# mixer.net
KiCad netlist of a schematic drawn in EAGLE
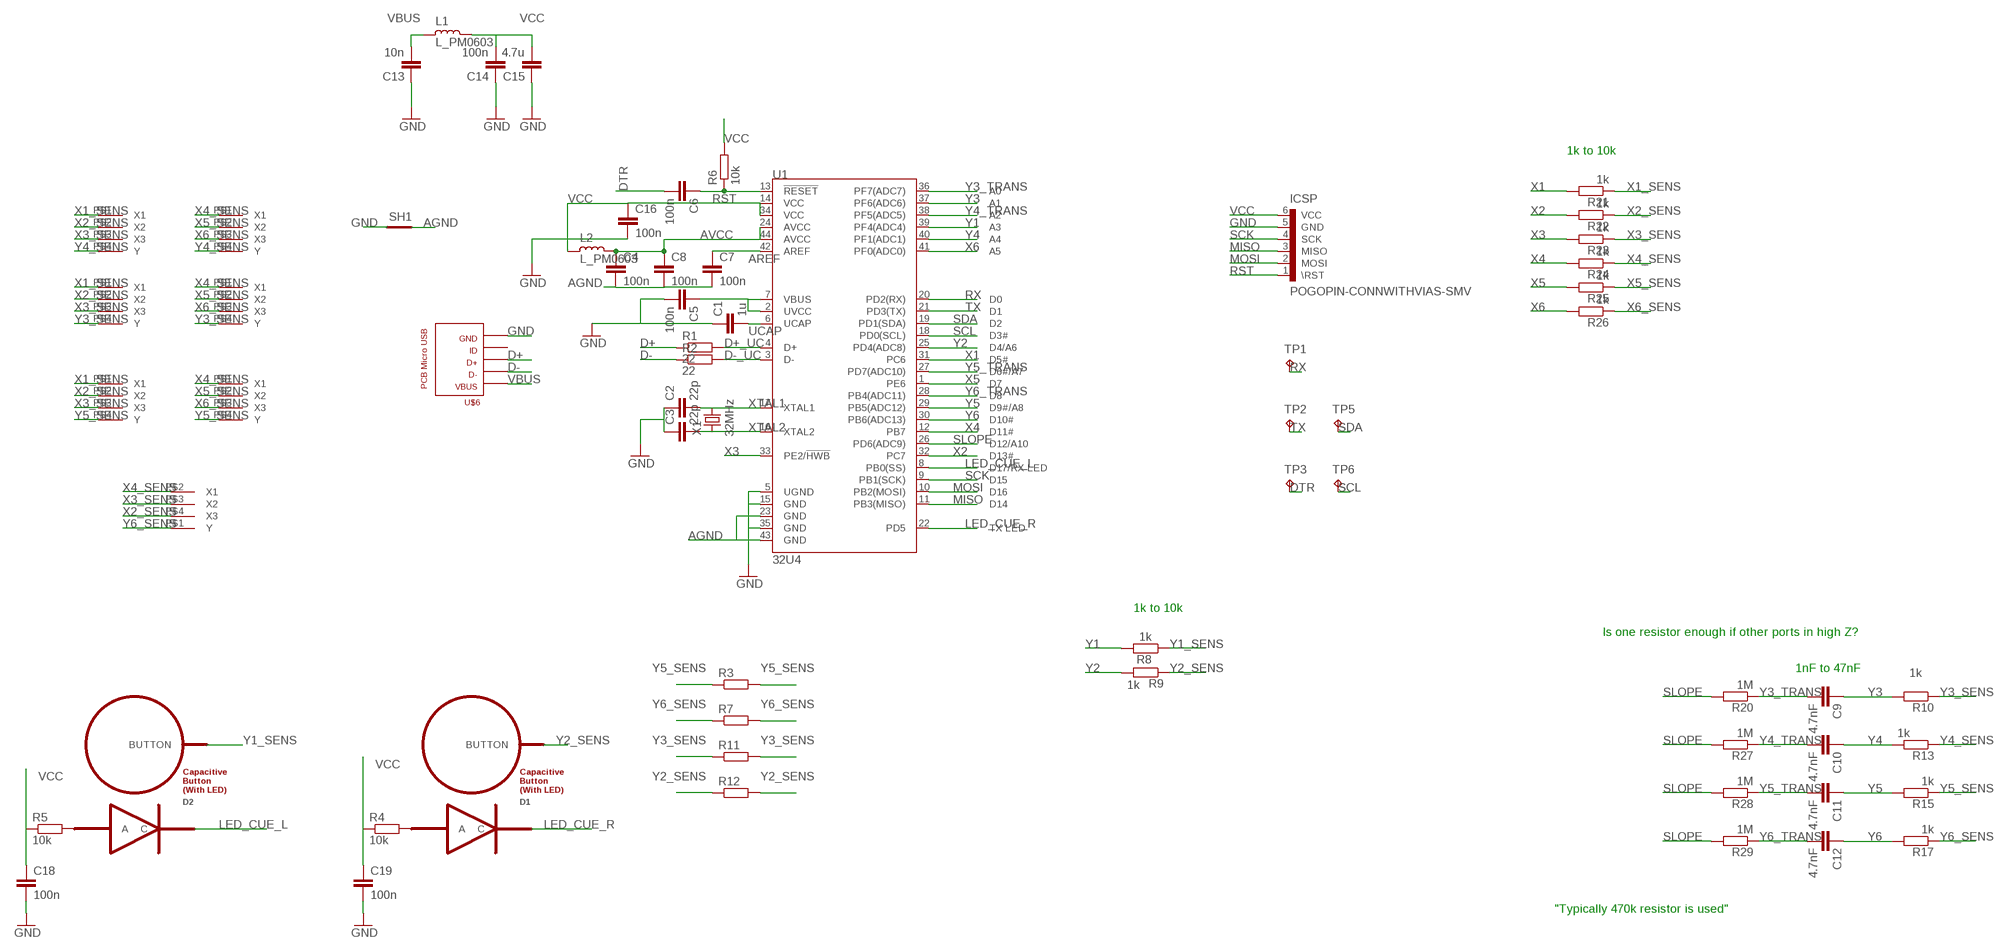
[diagram p0: schematic, sheet 1]

(export (version "E")
  (design (tool "Eeschema 10.0.6"))
  (components
    (comp (ref "C1")
      (value "1u")
      (footprint "eagle-import:C0402")
      (libsource (lib "eagle-import") (part "C-EUC0402"))
    )
    (comp (ref "C2")
      (value "22p")
      (footprint "eagle-import:C0402")
      (libsource (lib "eagle-import") (part "C-EUC0402"))
    )
    (comp (ref "C3")
      (value "22p")
      (footprint "eagle-import:C0402")
      (libsource (lib "eagle-import") (part "C-EUC0402"))
    )
    (comp (ref "C4")
      (value "100n")
      (footprint "eagle-import:C0402")
      (libsource (lib "eagle-import") (part "C-EUC0402"))
    )
    (comp (ref "C5")
      (value "100n")
      (footprint "eagle-import:C0402")
      (libsource (lib "eagle-import") (part "C-EUC0402"))
    )
    (comp (ref "C6")
      (value "100n")
      (footprint "eagle-import:C0402")
      (libsource (lib "eagle-import") (part "C-EUC0402"))
    )
    (comp (ref "C7")
      (value "100n")
      (footprint "eagle-import:C0402")
      (libsource (lib "eagle-import") (part "C-EUC0402"))
    )
    (comp (ref "C8")
      (value "100n")
      (footprint "eagle-import:C0402")
      (libsource (lib "eagle-import") (part "C-EUC0402"))
    )
    (comp (ref "C9")
      (value "4.7nF")
      (footprint "eagle-import:C0402")
      (libsource (lib "eagle-import") (part "C-EUC0402"))
    )
    (comp (ref "C10")
      (value "4.7nF")
      (footprint "eagle-import:C0402")
      (libsource (lib "eagle-import") (part "C-EUC0402"))
    )
    (comp (ref "C11")
      (value "4.7nF")
      (footprint "eagle-import:C0402")
      (libsource (lib "eagle-import") (part "C-EUC0402"))
    )
    (comp (ref "C12")
      (value "4.7nF")
      (footprint "eagle-import:C0402")
      (libsource (lib "eagle-import") (part "C-EUC0402"))
    )
    (comp (ref "C13")
      (value "10n")
      (footprint "eagle-import:C0402")
      (libsource (lib "eagle-import") (part "C-EUC0402"))
    )
    (comp (ref "C14")
      (value "100n")
      (footprint "eagle-import:C0402")
      (libsource (lib "eagle-import") (part "C-EUC0402"))
    )
    (comp (ref "C15")
      (value "4.7u")
      (footprint "eagle-import:C0402")
      (libsource (lib "eagle-import") (part "C-EUC0402"))
    )
    (comp (ref "C16")
      (value "100n")
      (footprint "eagle-import:C0402")
      (libsource (lib "eagle-import") (part "C-EUC0402"))
    )
    (comp (ref "C18")
      (value "100n")
      (footprint "eagle-import:C0402")
      (libsource (lib "eagle-import") (part "C-EUC0402"))
    )
    (comp (ref "C19")
      (value "100n")
      (footprint "eagle-import:C0402")
      (libsource (lib "eagle-import") (part "C-EUC0402"))
    )
    (comp (ref "D1")
      (value "LED_BUTTON")
      (footprint "eagle-import:LED_BUTTON")
      (libsource (lib "eagle-import") (part "LED_BUTTON"))
    )
    (comp (ref "D2")
      (value "LED_BUTTON")
      (footprint "eagle-import:LED_BUTTON")
      (libsource (lib "eagle-import") (part "LED_BUTTON"))
    )
    (comp (ref "ICSP")
      (value "POGOPIN-CONNWITHVIAS-SMV")
      (footprint "eagle-import:POGOPROG-CONN-OH-SMALLERVIAS")
      (libsource (lib "eagle-import") (part "POGOPIN-CONNWITHVIAS-SMV"))
    )
    (comp (ref "L1")
      (value "L_PM0603")
      (footprint "eagle-import:PM0603")
      (libsource (lib "eagle-import") (part "L_PM0603"))
    )
    (comp (ref "L2")
      (value "L_PM0603")
      (footprint "eagle-import:PM0603")
      (libsource (lib "eagle-import") (part "L_PM0603"))
    )
    (comp (ref "R1")
      (value "22")
      (footprint "eagle-import:R0402")
      (libsource (lib "eagle-import") (part "R-EU_R0402"))
    )
    (comp (ref "R2")
      (value "22")
      (footprint "eagle-import:R0402")
      (libsource (lib "eagle-import") (part "R-EU_R0402"))
    )
    (comp (ref "R3")
      (value "R-EU_R0603")
      (footprint "eagle-import:R0603")
      (libsource (lib "eagle-import") (part "R-EU_R0603"))
    )
    (comp (ref "R4")
      (value "10k")
      (footprint "eagle-import:R0402")
      (libsource (lib "eagle-import") (part "R-EU_R0402"))
    )
    (comp (ref "R5")
      (value "10k")
      (footprint "eagle-import:R0402")
      (libsource (lib "eagle-import") (part "R-EU_R0402"))
    )
    (comp (ref "R6")
      (value "10k")
      (footprint "eagle-import:R0402")
      (libsource (lib "eagle-import") (part "R-EU_R0402"))
    )
    (comp (ref "R7")
      (value "R-EU_R0603")
      (footprint "eagle-import:R0603")
      (libsource (lib "eagle-import") (part "R-EU_R0603"))
    )
    (comp (ref "R8")
      (value "1k")
      (footprint "eagle-import:R0402")
      (libsource (lib "eagle-import") (part "R-EU_R0402"))
    )
    (comp (ref "R9")
      (value "1k")
      (footprint "eagle-import:R0402")
      (libsource (lib "eagle-import") (part "R-EU_R0402"))
    )
    (comp (ref "R10")
      (value "1k")
      (footprint "eagle-import:R0402")
      (libsource (lib "eagle-import") (part "R-EU_R0402"))
    )
    (comp (ref "R11")
      (value "R-EU_R0603")
      (footprint "eagle-import:R0603")
      (libsource (lib "eagle-import") (part "R-EU_R0603"))
    )
    (comp (ref "R12")
      (value "R-EU_R0603")
      (footprint "eagle-import:R0603")
      (libsource (lib "eagle-import") (part "R-EU_R0603"))
    )
    (comp (ref "R13")
      (value "1k")
      (footprint "eagle-import:R0402")
      (libsource (lib "eagle-import") (part "R-EU_R0402"))
    )
    (comp (ref "R15")
      (value "1k")
      (footprint "eagle-import:R0402")
      (libsource (lib "eagle-import") (part "R-EU_R0402"))
    )
    (comp (ref "R17")
      (value "1k")
      (footprint "eagle-import:R0402")
      (libsource (lib "eagle-import") (part "R-EU_R0402"))
    )
    (comp (ref "R20")
      (value "1M")
      (footprint "eagle-import:R0402")
      (libsource (lib "eagle-import") (part "R-EU_R0402"))
    )
    (comp (ref "R21")
      (value "1k")
      (footprint "eagle-import:R0402")
      (libsource (lib "eagle-import") (part "R-EU_R0402"))
    )
    (comp (ref "R22")
      (value "1k")
      (footprint "eagle-import:R0402")
      (libsource (lib "eagle-import") (part "R-EU_R0402"))
    )
    (comp (ref "R23")
      (value "1k")
      (footprint "eagle-import:R0402")
      (libsource (lib "eagle-import") (part "R-EU_R0402"))
    )
    (comp (ref "R24")
      (value "1k")
      (footprint "eagle-import:R0402")
      (libsource (lib "eagle-import") (part "R-EU_R0402"))
    )
    (comp (ref "R25")
      (value "1k")
      (footprint "eagle-import:R0402")
      (libsource (lib "eagle-import") (part "R-EU_R0402"))
    )
    (comp (ref "R26")
      (value "1k")
      (footprint "eagle-import:R0402")
      (libsource (lib "eagle-import") (part "R-EU_R0402"))
    )
    (comp (ref "R27")
      (value "1M")
      (footprint "eagle-import:R0402")
      (libsource (lib "eagle-import") (part "R-EU_R0402"))
    )
    (comp (ref "R28")
      (value "1M")
      (footprint "eagle-import:R0402")
      (libsource (lib "eagle-import") (part "R-EU_R0402"))
    )
    (comp (ref "R29")
      (value "1M")
      (footprint "eagle-import:R0402")
      (libsource (lib "eagle-import") (part "R-EU_R0402"))
    )
    (comp (ref "SH1")
      (value "SHORT")
      (footprint "eagle-import:SHORT_TOP-6")
      (libsource (lib "eagle-import") (part "SHORT"))
    )
    (comp (ref "TP1")
      (value "TPTP06R")
      (footprint "eagle-import:TP06R")
      (libsource (lib "eagle-import") (part "TPTP06R"))
    )
    (comp (ref "TP2")
      (value "TPTP06R")
      (footprint "eagle-import:TP06R")
      (libsource (lib "eagle-import") (part "TPTP06R"))
    )
    (comp (ref "TP3")
      (value "TPTP06R")
      (footprint "eagle-import:TP06R")
      (libsource (lib "eagle-import") (part "TPTP06R"))
    )
    (comp (ref "TP5")
      (value "TPTP06R")
      (footprint "eagle-import:TP06R")
      (libsource (lib "eagle-import") (part "TPTP06R"))
    )
    (comp (ref "TP6")
      (value "TPTP06R")
      (footprint "eagle-import:TP06R")
      (libsource (lib "eagle-import") (part "TPTP06R"))
    )
    (comp (ref "U$1")
      (value "EQ_MUTUAL")
      (footprint "eagle-import:SMALL_EQ")
      (libsource (lib "eagle-import") (part "EQ_MUTUAL"))
    )
    (comp (ref "U$2")
      (value "EQ_MUTUAL")
      (footprint "eagle-import:SMALL_EQ")
      (libsource (lib "eagle-import") (part "EQ_MUTUAL"))
    )
    (comp (ref "U$3")
      (value "EQ_MUTUAL")
      (footprint "eagle-import:SMALL_EQ")
      (libsource (lib "eagle-import") (part "EQ_MUTUAL"))
    )
    (comp (ref "U$4")
      (value "EQ_MUTUAL")
      (footprint "eagle-import:SMALL_EQ")
      (libsource (lib "eagle-import") (part "EQ_MUTUAL"))
    )
    (comp (ref "U$5")
      (value "EQ_MUTUAL")
      (footprint "eagle-import:SMALL_EQ")
      (libsource (lib "eagle-import") (part "EQ_MUTUAL"))
    )
    (comp (ref "U$6")
      (value "PCB_MICRO_USB_BSS_2")
      (footprint "eagle-import:USB_TYPE_B_SS_2")
      (libsource (lib "eagle-import") (part "PCB_MICRO_USB_BSS_2"))
    )
    (comp (ref "U$7")
      (value "EQ_MUTUAL")
      (footprint "eagle-import:SMALL_EQ")
      (libsource (lib "eagle-import") (part "EQ_MUTUAL"))
    )
    (comp (ref "U$8")
      (value "SLIDER")
      (footprint "eagle-import:SLIDER")
      (libsource (lib "eagle-import") (part "SLIDER"))
    )
    (comp (ref "U1")
      (value "32U4")
      (footprint "eagle-import:QFN-44")
      (libsource (lib "eagle-import") (part "ATMEGA32U4QFN"))
    )
    (comp (ref "X1")
      (value "32MHz")
      (footprint "eagle-import:CRYSTAL-SMD-2.0X1.6MM")
      (libsource (lib "eagle-import") (part "CRYSTAL-32MHZ-SMD-2.0X1.6MM"))
    )
  )
  (nets
    (net (code "1") (name "/AGND") (class "Default")
      (node (ref "C4") (pin "2") (pinfunction "2_2") (pintype "passive"))
      (node (ref "C7") (pin "2") (pinfunction "2_2") (pintype "passive"))
      (node (ref "C8") (pin "2") (pinfunction "2_2") (pintype "passive"))
      (node (ref "SH1") (pin "2") (pinfunction "P$2_2") (pintype "bidirectional"))
      (node (ref "U1") (pin "23") (pinfunction "GND_23") (pintype "bidirectional"))
      (node (ref "U1") (pin "43") (pinfunction "GND_43") (pintype "bidirectional"))
    )
    (net (code "2") (name "/AREF") (class "Default")
      (node (ref "C7") (pin "1") (pinfunction "1_1") (pintype "passive"))
      (node (ref "U1") (pin "42") (pinfunction "AREF_42") (pintype "bidirectional"))
    )
    (net (code "3") (name "/AVCC") (class "Default")
      (node (ref "C4") (pin "1") (pinfunction "1_1") (pintype "passive"))
      (node (ref "C8") (pin "1") (pinfunction "1_1") (pintype "passive"))
      (node (ref "L2") (pin "1") (pinfunction "1_1") (pintype "passive"))
      (node (ref "U1") (pin "24") (pinfunction "AVCC_24") (pintype "bidirectional"))
      (node (ref "U1") (pin "44") (pinfunction "AVCC_44") (pintype "bidirectional"))
    )
    (net (code "4") (name "/D+") (class "Default")
      (node (ref "R1") (pin "1") (pinfunction "1_1") (pintype "passive"))
      (node (ref "U$6") (pin "3") (pinfunction "3_3") (pintype "bidirectional"))
    )
    (net (code "5") (name "/D+_UC") (class "Default")
      (node (ref "R1") (pin "2") (pinfunction "2_2") (pintype "passive"))
      (node (ref "U1") (pin "4") (pinfunction "D+_4") (pintype "bidirectional"))
    )
    (net (code "6") (name "/D-") (class "Default")
      (node (ref "R2") (pin "1") (pinfunction "1_1") (pintype "passive"))
      (node (ref "U$6") (pin "2") (pinfunction "2_2") (pintype "bidirectional"))
    )
    (net (code "7") (name "/D-_UC") (class "Default")
      (node (ref "R2") (pin "2") (pinfunction "2_2") (pintype "passive"))
      (node (ref "U1") (pin "3") (pinfunction "D-_3") (pintype "bidirectional"))
    )
    (net (code "8") (name "/DTR") (class "Default")
      (node (ref "C6") (pin "2") (pinfunction "2_2") (pintype "passive"))
      (node (ref "TP3") (pin "TP") (pinfunction "TP_TP") (pintype "input"))
    )
    (net (code "9") (name "/LED_CUE_L") (class "Default")
      (node (ref "D2") (pin "C") (pinfunction "C_C") (pintype "bidirectional"))
      (node (ref "U1") (pin "8") (pinfunction "PB0(SS)_8") (pintype "bidirectional"))
    )
    (net (code "10") (name "/LED_CUE_R") (class "Default")
      (node (ref "D1") (pin "C") (pinfunction "C_C") (pintype "bidirectional"))
      (node (ref "U1") (pin "22") (pinfunction "PD5_22") (pintype "bidirectional"))
    )
    (net (code "11") (name "/MISO") (class "Default")
      (node (ref "ICSP") (pin "3") (pinfunction "MISO_3") (pintype "bidirectional"))
      (node (ref "U1") (pin "11") (pinfunction "PB3(MISO)_11") (pintype "bidirectional"))
    )
    (net (code "12") (name "/MOSI") (class "Default")
      (node (ref "ICSP") (pin "2") (pinfunction "MOSI_2") (pintype "bidirectional"))
      (node (ref "U1") (pin "10") (pinfunction "PB2(MOSI)_10") (pintype "bidirectional"))
    )
    (net (code "13") (name "/RST") (class "Default")
      (node (ref "C6") (pin "1") (pinfunction "1_1") (pintype "passive"))
      (node (ref "ICSP") (pin "1") (pinfunction "\\RST_1") (pintype "bidirectional"))
      (node (ref "R6") (pin "1") (pinfunction "1_1") (pintype "passive"))
      (node (ref "U1") (pin "13") (pinfunction "~{RESET}_13") (pintype "bidirectional"))
    )
    (net (code "14") (name "/RX") (class "Default")
      (node (ref "TP1") (pin "TP") (pinfunction "TP_TP") (pintype "input"))
      (node (ref "U1") (pin "20") (pinfunction "PD2(RX)_20") (pintype "bidirectional"))
    )
    (net (code "15") (name "/SCK") (class "Default")
      (node (ref "ICSP") (pin "4") (pinfunction "SCK_4") (pintype "bidirectional"))
      (node (ref "U1") (pin "9") (pinfunction "PB1(SCK)_9") (pintype "bidirectional"))
    )
    (net (code "16") (name "/SCL") (class "Default")
      (node (ref "TP6") (pin "TP") (pinfunction "TP_TP") (pintype "input"))
      (node (ref "U1") (pin "18") (pinfunction "PD0(SCL)_18") (pintype "bidirectional"))
    )
    (net (code "17") (name "/SDA") (class "Default")
      (node (ref "TP5") (pin "TP") (pinfunction "TP_TP") (pintype "input"))
      (node (ref "U1") (pin "19") (pinfunction "PD1(SDA)_19") (pintype "bidirectional"))
    )
    (net (code "18") (name "/SLOPE") (class "Default")
      (node (ref "R20") (pin "2") (pinfunction "2_2") (pintype "passive"))
      (node (ref "R27") (pin "2") (pinfunction "2_2") (pintype "passive"))
      (node (ref "R28") (pin "2") (pinfunction "2_2") (pintype "passive"))
      (node (ref "R29") (pin "2") (pinfunction "2_2") (pintype "passive"))
      (node (ref "U1") (pin "26") (pinfunction "PD6(ADC9)_26") (pintype "bidirectional"))
    )
    (net (code "19") (name "/TX") (class "Default")
      (node (ref "TP2") (pin "TP") (pinfunction "TP_TP") (pintype "input"))
      (node (ref "U1") (pin "21") (pinfunction "PD3(TX)_21") (pintype "bidirectional"))
    )
    (net (code "20") (name "/UCAP") (class "Default")
      (node (ref "C1") (pin "2") (pinfunction "2_2") (pintype "passive"))
      (node (ref "U1") (pin "6") (pinfunction "UCAP_6") (pintype "bidirectional"))
    )
    (net (code "21") (name "/VBUS") (class "Default")
      (node (ref "C13") (pin "2") (pinfunction "2_2") (pintype "passive"))
      (node (ref "L1") (pin "2") (pinfunction "2_2") (pintype "passive"))
      (node (ref "U$6") (pin "1") (pinfunction "1_1") (pintype "bidirectional"))
    )
    (net (code "22") (name "/VCC") (class "Default")
      (node (ref "C14") (pin "2") (pinfunction "2_2") (pintype "passive"))
      (node (ref "C15") (pin "2") (pinfunction "2_2") (pintype "passive"))
      (node (ref "C16") (pin "1") (pinfunction "1_1") (pintype "passive"))
      (node (ref "C18") (pin "1") (pinfunction "1_1") (pintype "passive"))
      (node (ref "C19") (pin "1") (pinfunction "1_1") (pintype "passive"))
      (node (ref "C5") (pin "1") (pinfunction "1_1") (pintype "passive"))
      (node (ref "ICSP") (pin "6") (pinfunction "VCC_6") (pintype "bidirectional"))
      (node (ref "L1") (pin "1") (pinfunction "1_1") (pintype "passive"))
      (node (ref "L2") (pin "2") (pinfunction "2_2") (pintype "passive"))
      (node (ref "R4") (pin "1") (pinfunction "1_1") (pintype "passive"))
      (node (ref "R5") (pin "1") (pinfunction "1_1") (pintype "passive"))
      (node (ref "R6") (pin "2") (pinfunction "2_2") (pintype "passive"))
      (node (ref "U1") (pin "14") (pinfunction "VCC_14") (pintype "bidirectional"))
      (node (ref "U1") (pin "2") (pinfunction "UVCC_2") (pintype "bidirectional"))
      (node (ref "U1") (pin "34") (pinfunction "VCC_34") (pintype "bidirectional"))
      (node (ref "U1") (pin "7") (pinfunction "VBUS_7") (pintype "bidirectional"))
    )
    (net (code "23") (name "/X1") (class "Default")
      (node (ref "R21") (pin "2") (pinfunction "2_2") (pintype "passive"))
      (node (ref "U1") (pin "31") (pinfunction "PC6_31") (pintype "bidirectional"))
    )
    (net (code "24") (name "/X1_SENS") (class "Default")
      (node (ref "R21") (pin "1") (pinfunction "1_1") (pintype "passive"))
      (node (ref "U$1") (pin "P$1") (pinfunction "X1_P$1") (pintype "bidirectional"))
      (node (ref "U$2") (pin "P$1") (pinfunction "X1_P$1") (pintype "bidirectional"))
      (node (ref "U$3") (pin "P$1") (pinfunction "X1_P$1") (pintype "bidirectional"))
    )
    (net (code "25") (name "/X2") (class "Default")
      (node (ref "R22") (pin "2") (pinfunction "2_2") (pintype "passive"))
      (node (ref "U1") (pin "32") (pinfunction "PC7_32") (pintype "bidirectional"))
    )
    (net (code "26") (name "/X2_SENS") (class "Default")
      (node (ref "R22") (pin "1") (pinfunction "1_1") (pintype "passive"))
      (node (ref "U$1") (pin "P$2") (pinfunction "X2_P$2") (pintype "bidirectional"))
      (node (ref "U$2") (pin "P$2") (pinfunction "X2_P$2") (pintype "bidirectional"))
      (node (ref "U$3") (pin "P$2") (pinfunction "X2_P$2") (pintype "bidirectional"))
      (node (ref "U$8") (pin "P$4") (pinfunction "X3_P$4") (pintype "bidirectional"))
    )
    (net (code "27") (name "/X3") (class "Default")
      (node (ref "R23") (pin "2") (pinfunction "2_2") (pintype "passive"))
      (node (ref "U1") (pin "33") (pinfunction "PE2/~{HWB}_33") (pintype "bidirectional"))
    )
    (net (code "28") (name "/X3_SENS") (class "Default")
      (node (ref "R23") (pin "1") (pinfunction "1_1") (pintype "passive"))
      (node (ref "U$1") (pin "P$3") (pinfunction "X3_P$3") (pintype "bidirectional"))
      (node (ref "U$2") (pin "P$3") (pinfunction "X3_P$3") (pintype "bidirectional"))
      (node (ref "U$3") (pin "P$3") (pinfunction "X3_P$3") (pintype "bidirectional"))
      (node (ref "U$8") (pin "P$3") (pinfunction "X2_P$3") (pintype "bidirectional"))
    )
    (net (code "29") (name "/X4") (class "Default")
      (node (ref "R24") (pin "2") (pinfunction "2_2") (pintype "passive"))
      (node (ref "U1") (pin "12") (pinfunction "PB7_12") (pintype "bidirectional"))
    )
    (net (code "30") (name "/X4_SENS") (class "Default")
      (node (ref "R24") (pin "1") (pinfunction "1_1") (pintype "passive"))
      (node (ref "U$4") (pin "P$1") (pinfunction "X1_P$1") (pintype "bidirectional"))
      (node (ref "U$5") (pin "P$1") (pinfunction "X1_P$1") (pintype "bidirectional"))
      (node (ref "U$7") (pin "P$1") (pinfunction "X1_P$1") (pintype "bidirectional"))
      (node (ref "U$8") (pin "P$2") (pinfunction "X1_P$2") (pintype "bidirectional"))
    )
    (net (code "31") (name "/X5") (class "Default")
      (node (ref "R25") (pin "2") (pinfunction "2_2") (pintype "passive"))
      (node (ref "U1") (pin "1") (pinfunction "PE6_1") (pintype "bidirectional"))
    )
    (net (code "32") (name "/X5_SENS") (class "Default")
      (node (ref "R25") (pin "1") (pinfunction "1_1") (pintype "passive"))
      (node (ref "U$4") (pin "P$2") (pinfunction "X2_P$2") (pintype "bidirectional"))
      (node (ref "U$5") (pin "P$2") (pinfunction "X2_P$2") (pintype "bidirectional"))
      (node (ref "U$7") (pin "P$2") (pinfunction "X2_P$2") (pintype "bidirectional"))
    )
    (net (code "33") (name "/X6") (class "Default")
      (node (ref "R26") (pin "2") (pinfunction "2_2") (pintype "passive"))
      (node (ref "U1") (pin "41") (pinfunction "PF0(ADC0)_41") (pintype "bidirectional"))
    )
    (net (code "34") (name "/X6_SENS") (class "Default")
      (node (ref "R26") (pin "1") (pinfunction "1_1") (pintype "passive"))
      (node (ref "U$4") (pin "P$3") (pinfunction "X3_P$3") (pintype "bidirectional"))
      (node (ref "U$5") (pin "P$3") (pinfunction "X3_P$3") (pintype "bidirectional"))
      (node (ref "U$7") (pin "P$3") (pinfunction "X3_P$3") (pintype "bidirectional"))
    )
    (net (code "35") (name "/XTAL1") (class "Default")
      (node (ref "C2") (pin "2") (pinfunction "2_2") (pintype "passive"))
      (node (ref "U1") (pin "17") (pinfunction "XTAL1_17") (pintype "bidirectional"))
      (node (ref "X1") (pin "3") (pinfunction "2_3") (pintype "passive"))
    )
    (net (code "36") (name "/XTAL2") (class "Default")
      (node (ref "C3") (pin "2") (pinfunction "2_2") (pintype "passive"))
      (node (ref "U1") (pin "16") (pinfunction "XTAL2_16") (pintype "bidirectional"))
      (node (ref "X1") (pin "1") (pinfunction "1_1") (pintype "passive"))
    )
    (net (code "37") (name "/Y1") (class "Default")
      (node (ref "R8") (pin "2") (pinfunction "2_2") (pintype "passive"))
      (node (ref "U1") (pin "39") (pinfunction "PF4(ADC4)_39") (pintype "bidirectional"))
    )
    (net (code "38") (name "/Y1_SENS") (class "Default")
      (node (ref "D2") (pin "BUTTON") (pinfunction "BUTTON_BUTTON") (pintype "passive"))
      (node (ref "R8") (pin "1") (pinfunction "1_1") (pintype "passive"))
    )
    (net (code "39") (name "/Y2") (class "Default")
      (node (ref "R9") (pin "2") (pinfunction "2_2") (pintype "passive"))
      (node (ref "U1") (pin "25") (pinfunction "PD4(ADC8)_25") (pintype "bidirectional"))
    )
    (net (code "40") (name "/Y2_SENS") (class "Default")
      (node (ref "D1") (pin "BUTTON") (pinfunction "BUTTON_BUTTON") (pintype "passive"))
      (node (ref "R12") (pin "1") (pinfunction "1_1") (pintype "passive"))
      (node (ref "R12") (pin "2") (pinfunction "2_2") (pintype "passive"))
      (node (ref "R9") (pin "1") (pinfunction "1_1") (pintype "passive"))
    )
    (net (code "41") (name "/Y3") (class "Default")
      (node (ref "C9") (pin "1") (pinfunction "1_1") (pintype "passive"))
      (node (ref "R10") (pin "2") (pinfunction "2_2") (pintype "passive"))
      (node (ref "U1") (pin "37") (pinfunction "PF6(ADC6)_37") (pintype "bidirectional"))
    )
    (net (code "42") (name "/Y3_SENS") (class "Default")
      (node (ref "R10") (pin "1") (pinfunction "1_1") (pintype "passive"))
      (node (ref "R11") (pin "1") (pinfunction "1_1") (pintype "passive"))
      (node (ref "R11") (pin "2") (pinfunction "2_2") (pintype "passive"))
      (node (ref "U$2") (pin "P$4") (pinfunction "Y_P$4") (pintype "bidirectional"))
      (node (ref "U$5") (pin "P$4") (pinfunction "Y_P$4") (pintype "bidirectional"))
    )
    (net (code "43") (name "/Y3_TRANS") (class "Default")
      (node (ref "C9") (pin "2") (pinfunction "2_2") (pintype "passive"))
      (node (ref "R20") (pin "1") (pinfunction "1_1") (pintype "passive"))
      (node (ref "U1") (pin "36") (pinfunction "PF7(ADC7)_36") (pintype "bidirectional"))
    )
    (net (code "44") (name "/Y4") (class "Default")
      (node (ref "C10") (pin "1") (pinfunction "1_1") (pintype "passive"))
      (node (ref "R13") (pin "2") (pinfunction "2_2") (pintype "passive"))
      (node (ref "U1") (pin "40") (pinfunction "PF1(ADC1)_40") (pintype "bidirectional"))
    )
    (net (code "45") (name "/Y4_SENS") (class "Default")
      (node (ref "R13") (pin "1") (pinfunction "1_1") (pintype "passive"))
      (node (ref "U$1") (pin "P$4") (pinfunction "Y_P$4") (pintype "bidirectional"))
      (node (ref "U$4") (pin "P$4") (pinfunction "Y_P$4") (pintype "bidirectional"))
    )
    (net (code "46") (name "/Y4_TRANS") (class "Default")
      (node (ref "C10") (pin "2") (pinfunction "2_2") (pintype "passive"))
      (node (ref "R27") (pin "1") (pinfunction "1_1") (pintype "passive"))
      (node (ref "U1") (pin "38") (pinfunction "PF5(ADC5)_38") (pintype "bidirectional"))
    )
    (net (code "47") (name "/Y5") (class "Default")
      (node (ref "C11") (pin "1") (pinfunction "1_1") (pintype "passive"))
      (node (ref "R15") (pin "2") (pinfunction "2_2") (pintype "passive"))
      (node (ref "U1") (pin "29") (pinfunction "PB5(ADC12)_29") (pintype "bidirectional"))
    )
    (net (code "48") (name "/Y5_SENS") (class "Default")
      (node (ref "R15") (pin "1") (pinfunction "1_1") (pintype "passive"))
      (node (ref "R3") (pin "1") (pinfunction "1_1") (pintype "passive"))
      (node (ref "R3") (pin "2") (pinfunction "2_2") (pintype "passive"))
      (node (ref "U$3") (pin "P$4") (pinfunction "Y_P$4") (pintype "bidirectional"))
      (node (ref "U$7") (pin "P$4") (pinfunction "Y_P$4") (pintype "bidirectional"))
    )
    (net (code "49") (name "/Y5_TRANS") (class "Default")
      (node (ref "C11") (pin "2") (pinfunction "2_2") (pintype "passive"))
      (node (ref "R28") (pin "1") (pinfunction "1_1") (pintype "passive"))
      (node (ref "U1") (pin "27") (pinfunction "PD7(ADC10)_27") (pintype "bidirectional"))
    )
    (net (code "50") (name "/Y6") (class "Default")
      (node (ref "C12") (pin "1") (pinfunction "1_1") (pintype "passive"))
      (node (ref "R17") (pin "2") (pinfunction "2_2") (pintype "passive"))
      (node (ref "U1") (pin "30") (pinfunction "PB6(ADC13)_30") (pintype "bidirectional"))
    )
    (net (code "51") (name "/Y6_SENS") (class "Default")
      (node (ref "R17") (pin "1") (pinfunction "1_1") (pintype "passive"))
      (node (ref "R7") (pin "1") (pinfunction "1_1") (pintype "passive"))
      (node (ref "R7") (pin "2") (pinfunction "2_2") (pintype "passive"))
      (node (ref "U$8") (pin "P$1") (pinfunction "Y_P$1") (pintype "bidirectional"))
    )
    (net (code "52") (name "/Y6_TRANS") (class "Default")
      (node (ref "C12") (pin "2") (pinfunction "2_2") (pintype "passive"))
      (node (ref "R29") (pin "1") (pinfunction "1_1") (pintype "passive"))
      (node (ref "U1") (pin "28") (pinfunction "PB4(ADC11)_28") (pintype "bidirectional"))
    )
    (net (code "53") (name "GND") (class "Default")
      (node (ref "C1") (pin "1") (pinfunction "1_1") (pintype "passive"))
      (node (ref "C13") (pin "1") (pinfunction "1_1") (pintype "passive"))
      (node (ref "C14") (pin "1") (pinfunction "1_1") (pintype "passive"))
      (node (ref "C15") (pin "1") (pinfunction "1_1") (pintype "passive"))
      (node (ref "C16") (pin "2") (pinfunction "2_2") (pintype "passive"))
      (node (ref "C18") (pin "2") (pinfunction "2_2") (pintype "passive"))
      (node (ref "C19") (pin "2") (pinfunction "2_2") (pintype "passive"))
      (node (ref "C2") (pin "1") (pinfunction "1_1") (pintype "passive"))
      (node (ref "C3") (pin "1") (pinfunction "1_1") (pintype "passive"))
      (node (ref "C5") (pin "2") (pinfunction "2_2") (pintype "passive"))
      (node (ref "ICSP") (pin "5") (pinfunction "GND_5") (pintype "bidirectional"))
      (node (ref "SH1") (pin "1") (pinfunction "P$1_1") (pintype "bidirectional"))
      (node (ref "U$6") (pin "5") (pinfunction "5_5") (pintype "bidirectional"))
      (node (ref "U1") (pin "15") (pinfunction "GND_15") (pintype "bidirectional"))
      (node (ref "U1") (pin "35") (pinfunction "GND_35") (pintype "bidirectional"))
      (node (ref "U1") (pin "5") (pinfunction "UGND_5") (pintype "bidirectional"))
    )
    (net (code "54") (name "Net-(D1-PadA)") (class "Default")
      (node (ref "D1") (pin "A") (pinfunction "A_A") (pintype "bidirectional"))
      (node (ref "R4") (pin "2") (pinfunction "2_2") (pintype "passive"))
    )
    (net (code "55") (name "Net-(D2-PadA)") (class "Default")
      (node (ref "D2") (pin "A") (pinfunction "A_A") (pintype "bidirectional"))
      (node (ref "R5") (pin "2") (pinfunction "2_2") (pintype "passive"))
    )
    (net (code "56") (name "unconnected-(U$6-Pad4)") (class "Default")
      (node (ref "U$6") (pin "4") (pinfunction "4_4") (pintype "bidirectional"))
    )
  )
)
